# signal_path.net
KiCad netlist of a schematic drawn in Altium Designer
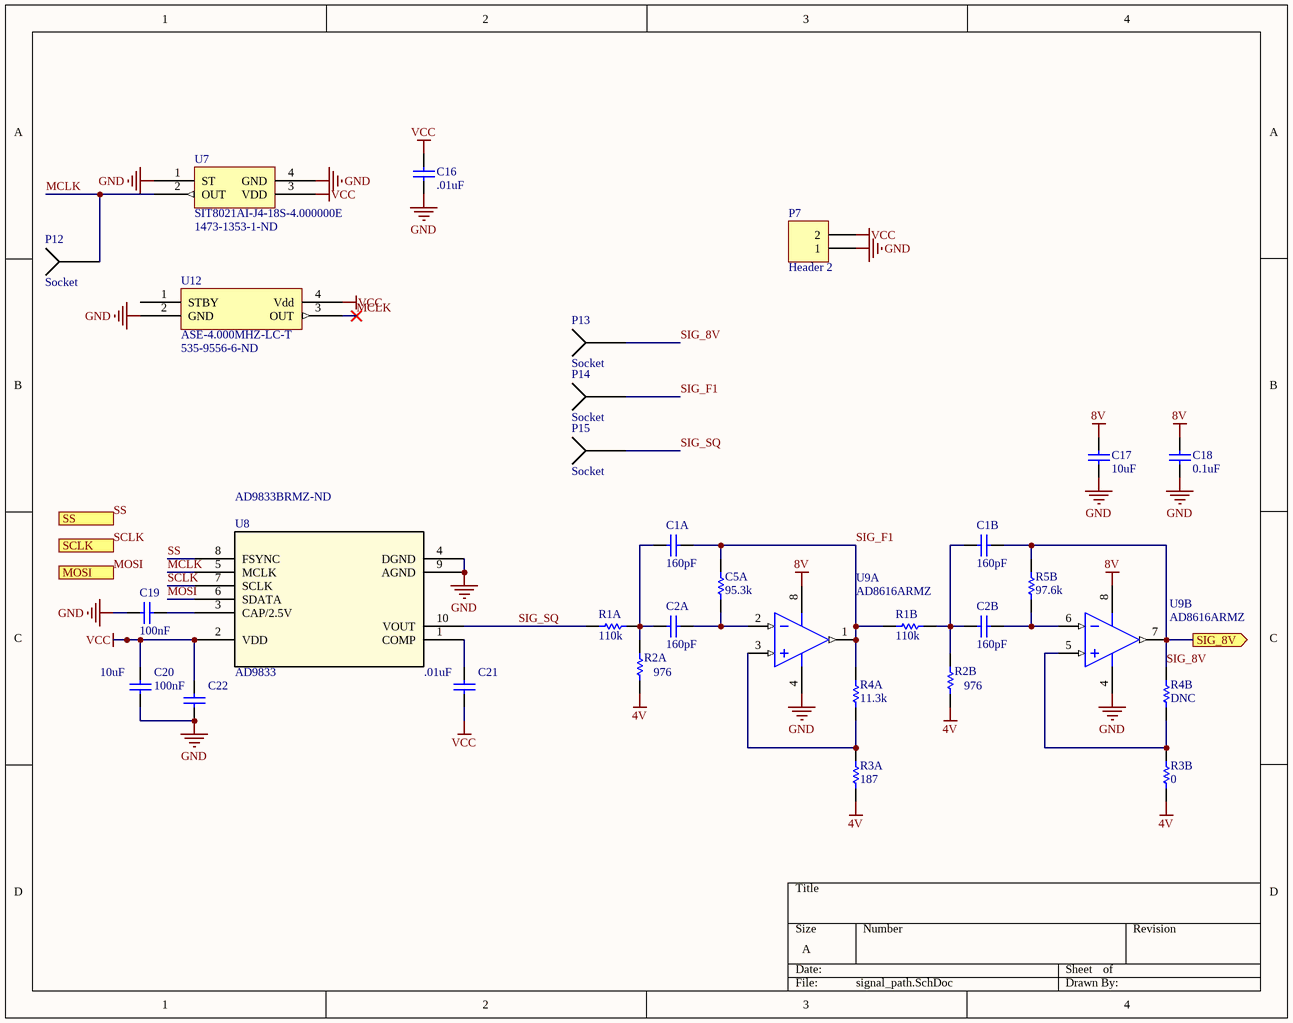
[diagram p0: signal_path.SchDoc]

(export (version "E")
  (design (tool "Eeschema 10.0.6"))
  (components
    (comp (ref "C1A")
      (value "160pF")
      (footprint "0603")
      (description "Ceramic Capacitor (Surface Mount)")
      (fields (field (name "MANUFACTURER") "Generic Ceramic Chip Cap (TBD)") (field (name "Comment") "Cap"))
      (libsource (lib "maglib") (part "Cap"))
    )
    (comp (ref "C1B")
      (value "160pF")
      (footprint "0603")
      (description "Ceramic Capacitor (Surface Mount)")
      (fields (field (name "MANUFACTURER") "Generic Ceramic Chip Cap (TBD)") (field (name "Comment") "Cap"))
      (libsource (lib "maglib") (part "Cap"))
    )
    (comp (ref "C2A")
      (value "160pF")
      (footprint "0603")
      (description "Ceramic Capacitor (Surface Mount)")
      (fields (field (name "MANUFACTURER") "Generic Ceramic Chip Cap (TBD)") (field (name "Comment") "Cap"))
      (libsource (lib "maglib") (part "Cap"))
    )
    (comp (ref "C2B")
      (value "160pF")
      (footprint "0603")
      (description "Ceramic Capacitor (Surface Mount)")
      (fields (field (name "MANUFACTURER") "Generic Ceramic Chip Cap (TBD)") (field (name "Comment") "Cap"))
      (libsource (lib "maglib") (part "Cap"))
    )
    (comp (ref "C5A")
      (value "95.3k")
      (footprint "0603")
      (description "Chip Resistor (Surface Mount)")
      (fields (field (name "MANUFACTURER") "Generic Chip Res (TBD)") (field (name "Comment") "Res"))
      (libsource (lib "maglib") (part "Res"))
    )
    (comp (ref "C16")
      (value ".01uF")
      (footprint "0603")
      (description "Ceramic Capacitor (Surface Mount)")
      (fields (field (name "MANUFACTURER") "Generic Ceramic Chip Cap (TBD)") (field (name "Comment") "Cap"))
      (libsource (lib "maglib") (part "Cap"))
    )
    (comp (ref "C17")
      (value "10uF")
      (footprint "0603")
      (description "Ceramic Capacitor (Surface Mount)")
      (fields (field (name "MANUFACTURER") "Generic Ceramic Chip Cap (TBD)") (field (name "Comment") "Cap"))
      (libsource (lib "maglib") (part "Cap"))
    )
    (comp (ref "C18")
      (value "0.1uF")
      (footprint "0603")
      (description "Ceramic Capacitor (Surface Mount)")
      (fields (field (name "MANUFACTURER") "Generic Ceramic Chip Cap (TBD)") (field (name "Comment") "Cap"))
      (libsource (lib "maglib") (part "Cap"))
    )
    (comp (ref "C19")
      (value "100nF")
      (footprint "0603")
      (description "Ceramic Capacitor (Surface Mount)")
      (fields (field (name "MANUFACTURER") "Generic Ceramic Chip Cap (TBD)") (field (name "Comment") "Cap"))
      (libsource (lib "maglib") (part "Cap"))
    )
    (comp (ref "C20")
      (value "10uF")
      (footprint "0603")
      (description "Ceramic Capacitor (Surface Mount)")
      (fields (field (name "MANUFACTURER") "Generic Ceramic Chip Cap (TBD)") (field (name "Comment") "Cap"))
      (libsource (lib "maglib") (part "Cap"))
    )
    (comp (ref "C21")
      (value ".01uF")
      (footprint "0603")
      (description "Ceramic Capacitor (Surface Mount)")
      (fields (field (name "MANUFACTURER") "Generic Ceramic Chip Cap (TBD)") (field (name "Comment") "Cap"))
      (libsource (lib "maglib") (part "Cap"))
    )
    (comp (ref "C22")
      (value "100nF")
      (footprint "0603")
      (description "Ceramic Capacitor (Surface Mount)")
      (fields (field (name "MANUFACTURER") "Generic Ceramic Chip Cap (TBD)") (field (name "Comment") "Cap"))
      (libsource (lib "maglib") (part "Cap"))
    )
    (comp (ref "P7")
      (value "Header 2")
      (footprint "HDR1X2")
      (description "Header, 2-Pin")
      (fields (field (name "PUBLISHER") "Altium Limited"))
      (libsource (lib "Miscellaneous Connectors") (part "Header 2"))
    )
    (comp (ref "P12") (value "Socket") (footprint "socket") (libsource (lib "maglib") (part "Socket")))
    (comp (ref "P13") (value "Socket") (footprint "socket") (libsource (lib "maglib") (part "Socket")))
    (comp (ref "P14") (value "Socket") (footprint "socket") (libsource (lib "maglib") (part "Socket")))
    (comp (ref "P15") (value "Socket") (footprint "socket") (libsource (lib "maglib") (part "Socket")))
    (comp (ref "R1A")
      (value "110k")
      (footprint "0603")
      (description "Chip Resistor (Surface Mount)")
      (fields (field (name "MANUFACTURER") "Generic Chip Res (TBD)") (field (name "Comment") "Res"))
      (libsource (lib "maglib") (part "Res"))
    )
    (comp (ref "R1B")
      (value "110k")
      (footprint "0603")
      (description "Chip Resistor (Surface Mount)")
      (fields (field (name "MANUFACTURER") "Generic Chip Res (TBD)") (field (name "Comment") "Res"))
      (libsource (lib "maglib") (part "Res"))
    )
    (comp (ref "R2A")
      (value "976")
      (footprint "0603")
      (description "Chip Resistor (Surface Mount)")
      (fields (field (name "MANUFACTURER") "Generic Chip Res (TBD)") (field (name "Comment") "Res"))
      (libsource (lib "maglib") (part "Res"))
    )
    (comp (ref "R2B")
      (value "976")
      (footprint "0603")
      (description "Chip Resistor (Surface Mount)")
      (fields (field (name "MANUFACTURER") "Generic Chip Res (TBD)") (field (name "Comment") "Res"))
      (libsource (lib "maglib") (part "Res"))
    )
    (comp (ref "R3A")
      (value "187")
      (footprint "0603")
      (description "Chip Resistor (Surface Mount)")
      (fields (field (name "MANUFACTURER") "Generic Chip Res (TBD)") (field (name "Comment") "Res"))
      (libsource (lib "maglib") (part "Res"))
    )
    (comp (ref "R3B")
      (value "0")
      (footprint "0603")
      (description "Chip Resistor (Surface Mount)")
      (fields (field (name "MANUFACTURER") "Generic Chip Res (TBD)") (field (name "Comment") "Res"))
      (libsource (lib "maglib") (part "Res"))
    )
    (comp (ref "R4A")
      (value "11.3k")
      (footprint "0603")
      (description "Chip Resistor (Surface Mount)")
      (fields (field (name "MANUFACTURER") "Generic Chip Res (TBD)") (field (name "Comment") "Res"))
      (libsource (lib "maglib") (part "Res"))
    )
    (comp (ref "R4B")
      (value "DNC")
      (footprint "0603")
      (description "Chip Resistor (Surface Mount)")
      (fields (field (name "MANUFACTURER") "Generic Chip Res (TBD)") (field (name "Comment") "Res"))
      (libsource (lib "maglib") (part "Res"))
    )
    (comp (ref "R5B")
      (value "97.6k")
      (footprint "0603")
      (description "Chip Resistor (Surface Mount)")
      (fields (field (name "MANUFACTURER") "Generic Chip Res (TBD)") (field (name "Comment") "Res"))
      (libsource (lib "maglib") (part "Res"))
    )
    (comp (ref "U7")
      (value "SIT8021AI-J4-18S-4.000000E")
      (footprint "SiT8021 - BGA4C100P2X2_154X84X60")
      (description "4 MHz low power oscillator")
      (fields (field (name "SUPPLIER PART NUMBER 1") "1473-1353-1-ND"))
      (libsource (lib "maglib") (part "SIT8021AI-J4-18S-4.000000E"))
    )
    (comp (ref "U8")
      (value "AD9833")
      (footprint "MSOP-10")
      (description "MSOP-10")
      (fields (field (name "SUPPLIER PART NUMBER 1") "AD9833BRMZ-ND"))
      (libsource (lib "maglib") (part "AD9833"))
    )
    (comp (ref "U9")
      (value "AD8616ARMZ")
      (footprint "ADI-RM-8_M")
      (fields (field (name "GENERIC PART NUMBER") "AD8616") (field (name "MANUFACTURER") "Analog Devices"))
      (libsource (lib "Altium Content Vault") (part "ADI-OP29X-R-8"))
    )
    (comp (ref "U12")
      (value "ASE-4.000MHZ-LC-T")
      (footprint "DFN165P250X120-4N")
      (description "4 MHz SMD Oscillator")
      (fields (field (name "SUPPLIER PART NUMBER 1") "535-9556-6-ND"))
      (libsource (lib "maglib") (part "ASE-4.000MHZ-LC-T"))
    )
  )
  (nets
    (net (code "1") (name "/MCLK") (class "Default")
      (node (ref "P12") (pin "0") (pinfunction "0_0") (pintype "passive"))
      (node (ref "U12") (pin "3") (pinfunction "OUT_3") (pintype "output"))
      (node (ref "U7") (pin "2") (pinfunction "OUT_2") (pintype "output"))
      (node (ref "U8") (pin "5") (pinfunction "MCLK_5") (pintype "passive"))
    )
    (net (code "2") (name "/MOSI") (class "Default")
      (node (ref "U8") (pin "6") (pinfunction "SDATA_6") (pintype "passive"))
    )
    (net (code "3") (name "/SCLK") (class "Default")
      (node (ref "U8") (pin "7") (pinfunction "SCLK_7") (pintype "passive"))
    )
    (net (code "4") (name "/SIG_8V") (class "Default")
      (node (ref "C1B") (pin "2") (pinfunction "2_2") (pintype "passive"))
      (node (ref "P13") (pin "0") (pinfunction "0_0") (pintype "passive"))
      (node (ref "R4B") (pin "2") (pinfunction "2_2") (pintype "passive"))
      (node (ref "R5B") (pin "2") (pinfunction "2_2") (pintype "passive"))
      (node (ref "U9") (pin "7") (pinfunction "OUT_B_7") (pintype "output"))
    )
    (net (code "5") (name "/SIG_F1") (class "Default")
      (node (ref "C1A") (pin "2") (pinfunction "2_2") (pintype "passive"))
      (node (ref "C5A") (pin "2") (pinfunction "2_2") (pintype "passive"))
      (node (ref "P14") (pin "0") (pinfunction "0_0") (pintype "passive"))
      (node (ref "R1B") (pin "1") (pinfunction "1_1") (pintype "passive"))
      (node (ref "R4A") (pin "2") (pinfunction "2_2") (pintype "passive"))
      (node (ref "U9") (pin "1") (pinfunction "OUT_A_1") (pintype "output"))
    )
    (net (code "6") (name "/SIG_SQ") (class "Default")
      (node (ref "P15") (pin "0") (pinfunction "0_0") (pintype "passive"))
      (node (ref "R1A") (pin "1") (pinfunction "1_1") (pintype "passive"))
      (node (ref "U8") (pin "10") (pinfunction "VOUT_10") (pintype "passive"))
    )
    (net (code "7") (name "/SS") (class "Default")
      (node (ref "U8") (pin "8") (pinfunction "FSYNC_8") (pintype "passive"))
    )
    (net (code "8") (name "4V") (class "Default")
      (node (ref "R2A") (pin "1") (pinfunction "1_1") (pintype "passive"))
      (node (ref "R2B") (pin "1") (pinfunction "1_1") (pintype "passive"))
      (node (ref "R3A") (pin "1") (pinfunction "1_1") (pintype "passive"))
      (node (ref "R3B") (pin "1") (pinfunction "1_1") (pintype "passive"))
    )
    (net (code "9") (name "8V") (class "Default")
      (node (ref "C17") (pin "1") (pinfunction "1_1") (pintype "passive"))
      (node (ref "C18") (pin "1") (pinfunction "1_1") (pintype "passive"))
      (node (ref "U9") (pin "8") (pinfunction "+V_8") (pintype "power_in"))
    )
    (net (code "10") (name "GND") (class "Default")
      (node (ref "C16") (pin "2") (pinfunction "2_2") (pintype "passive"))
      (node (ref "C17") (pin "2") (pinfunction "2_2") (pintype "passive"))
      (node (ref "C18") (pin "2") (pinfunction "2_2") (pintype "passive"))
      (node (ref "C19") (pin "1") (pinfunction "1_1") (pintype "passive"))
      (node (ref "C20") (pin "2") (pinfunction "2_2") (pintype "passive"))
      (node (ref "C22") (pin "2") (pinfunction "2_2") (pintype "passive"))
      (node (ref "P7") (pin "1") (pinfunction "1_1") (pintype "passive"))
      (node (ref "U12") (pin "2") (pinfunction "GND_2") (pintype "power_in"))
      (node (ref "U7") (pin "1") (pinfunction "ST_1") (pintype "passive"))
      (node (ref "U7") (pin "4") (pinfunction "GND_4") (pintype "power_in"))
      (node (ref "U8") (pin "4") (pinfunction "DGND_4") (pintype "passive"))
      (node (ref "U8") (pin "9") (pinfunction "AGND_9") (pintype "passive"))
      (node (ref "U9") (pin "4") (pinfunction "-V_4") (pintype "power_in"))
    )
    (net (code "11") (name "Net-(C1A-Pad1)") (class "Default")
      (node (ref "C1A") (pin "1") (pinfunction "1_1") (pintype "passive"))
      (node (ref "C2A") (pin "1") (pinfunction "1_1") (pintype "passive"))
      (node (ref "R1A") (pin "2") (pinfunction "2_2") (pintype "passive"))
      (node (ref "R2A") (pin "2") (pinfunction "2_2") (pintype "passive"))
    )
    (net (code "12") (name "Net-(C1B-Pad1)") (class "Default")
      (node (ref "C1B") (pin "1") (pinfunction "1_1") (pintype "passive"))
      (node (ref "C2B") (pin "1") (pinfunction "1_1") (pintype "passive"))
      (node (ref "R1B") (pin "2") (pinfunction "2_2") (pintype "passive"))
      (node (ref "R2B") (pin "2") (pinfunction "2_2") (pintype "passive"))
    )
    (net (code "13") (name "Net-(U8-CAP{slash}2.5V)") (class "Default")
      (node (ref "C19") (pin "2") (pinfunction "2_2") (pintype "passive"))
      (node (ref "U8") (pin "3") (pinfunction "CAP/2.5V_3") (pintype "power_in"))
    )
    (net (code "14") (name "Net-(U8-COMP)") (class "Default")
      (node (ref "C21") (pin "1") (pinfunction "1_1") (pintype "passive"))
      (node (ref "U8") (pin "1") (pinfunction "COMP_1") (pintype "passive"))
    )
    (net (code "15") (name "Net-(U9A-+IN_A)") (class "Default")
      (node (ref "R3A") (pin "2") (pinfunction "2_2") (pintype "passive"))
      (node (ref "R4A") (pin "1") (pinfunction "1_1") (pintype "passive"))
      (node (ref "U9") (pin "3") (pinfunction "+IN_A_3") (pintype "input"))
    )
    (net (code "16") (name "Net-(U9A--IN_A)") (class "Default")
      (node (ref "C2A") (pin "2") (pinfunction "2_2") (pintype "passive"))
      (node (ref "C5A") (pin "1") (pinfunction "1_1") (pintype "passive"))
      (node (ref "U9") (pin "2") (pinfunction "-IN_A_2") (pintype "input"))
    )
    (net (code "17") (name "Net-(U9B-+IN_B)") (class "Default")
      (node (ref "R3B") (pin "2") (pinfunction "2_2") (pintype "passive"))
      (node (ref "R4B") (pin "1") (pinfunction "1_1") (pintype "passive"))
      (node (ref "U9") (pin "5") (pinfunction "+IN_B_5") (pintype "input"))
    )
    (net (code "18") (name "Net-(U9B--IN_B)") (class "Default")
      (node (ref "C2B") (pin "2") (pinfunction "2_2") (pintype "passive"))
      (node (ref "R5B") (pin "1") (pinfunction "1_1") (pintype "passive"))
      (node (ref "U9") (pin "6") (pinfunction "-IN_B_6") (pintype "input"))
    )
    (net (code "19") (name "VCC") (class "Default")
      (node (ref "C16") (pin "1") (pinfunction "1_1") (pintype "passive"))
      (node (ref "C20") (pin "1") (pinfunction "1_1") (pintype "passive"))
      (node (ref "C21") (pin "2") (pinfunction "2_2") (pintype "passive"))
      (node (ref "C22") (pin "1") (pinfunction "1_1") (pintype "passive"))
      (node (ref "P7") (pin "2") (pinfunction "2_2") (pintype "passive"))
      (node (ref "U12") (pin "4") (pinfunction "Vdd_4") (pintype "power_in"))
      (node (ref "U7") (pin "3") (pinfunction "VDD_3") (pintype "power_in"))
      (node (ref "U8") (pin "2") (pinfunction "VDD_2") (pintype "power_in"))
    )
    (net (code "20") (name "unconnected-(U12-STBY-Pad1)") (class "Default")
      (node (ref "U12") (pin "1") (pinfunction "STBY_1") (pintype "passive"))
    )
  )
)
